# power_pcb.net
KiCad netlist of a schematic drawn in EAGLE
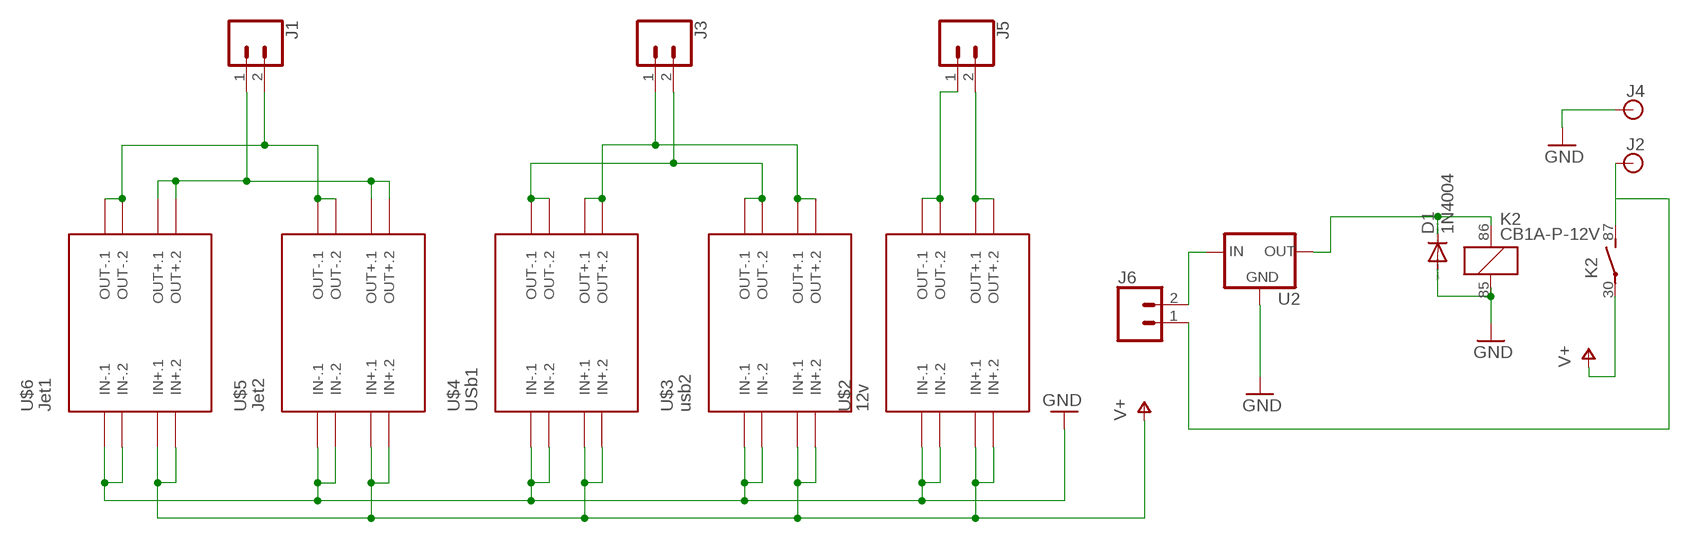
[diagram p0: schematic, sheet 1]

(export (version "E")
  (design (tool "Eeschema 10.0.6"))
  (components
    (comp (ref "D1")
      (value "1N4004")
      (footprint "eagle-import:DO41-10")
      (libsource (lib "eagle-import") (part "1N4004"))
    )
    (comp (ref "J1")
      (value "CONN_025MM")
      (footprint "eagle-import:SCREWTERMINAL-5MM-2")
      (libsource (lib "eagle-import") (part "CONN_025MM"))
    )
    (comp (ref "J2")
      (value "BANANA_CONN")
      (footprint "eagle-import:BANANA_CONN")
      (libsource (lib "eagle-import") (part "BANANA_CONN"))
    )
    (comp (ref "J3")
      (value "CONN_025MM")
      (footprint "eagle-import:SCREWTERMINAL-5MM-2")
      (libsource (lib "eagle-import") (part "CONN_025MM"))
    )
    (comp (ref "J4")
      (value "BANANA_CONN")
      (footprint "eagle-import:BANANA_CONN")
      (libsource (lib "eagle-import") (part "BANANA_CONN"))
    )
    (comp (ref "J5")
      (value "CONN_025MM")
      (footprint "eagle-import:SCREWTERMINAL-5MM-2")
      (libsource (lib "eagle-import") (part "CONN_025MM"))
    )
    (comp (ref "J6")
      (value "CONN_025MM")
      (footprint "eagle-import:SCREWTERMINAL-5MM-2")
      (libsource (lib "eagle-import") (part "CONN_025MM"))
    )
    (comp (ref "K2")
      (value "CB1A-P-12V")
      (footprint "eagle-import:CB1")
      (fields (field (name "MF") "AROMAT/ MATSUSHITA"))
      (libsource (lib "eagle-import") (part "CB1A-P-12V"))
    )
    (comp (ref "U$2")
      (value "12v")
      (footprint "eagle-import:DC-DC-STEP-DOWN-MP1584")
      (libsource (lib "eagle-import") (part "DC-DC-STEP-DOWN-MP1584"))
    )
    (comp (ref "U$3")
      (value "usb2")
      (footprint "eagle-import:DC-DC-STEP-DOWN-MP1584")
      (libsource (lib "eagle-import") (part "DC-DC-STEP-DOWN-MP1584"))
    )
    (comp (ref "U$4")
      (value "USb1")
      (footprint "eagle-import:DC-DC-STEP-DOWN-MP1584")
      (libsource (lib "eagle-import") (part "DC-DC-STEP-DOWN-MP1584"))
    )
    (comp (ref "U$5")
      (value "Jet2")
      (footprint "eagle-import:DC-DC-STEP-DOWN-MP1584")
      (libsource (lib "eagle-import") (part "DC-DC-STEP-DOWN-MP1584"))
    )
    (comp (ref "U$6")
      (value "Jet1")
      (footprint "eagle-import:DC-DC-STEP-DOWN-MP1584")
      (libsource (lib "eagle-import") (part "DC-DC-STEP-DOWN-MP1584"))
    )
    (comp (ref "U2")
      (value "V_REG_78XXSINK")
      (footprint "eagle-import:TO220-IGO")
      (libsource (lib "eagle-import") (part "V_REG_78XXSINK"))
    )
  )
  (nets
    (net (code "1") (name "GND") (class "Default")
      (node (ref "D1") (pin "A") (pinfunction "A_A") (pintype "passive"))
      (node (ref "J4") (pin "P$1") (pinfunction "1_P$1") (pintype "passive"))
      (node (ref "K2") (pin "85") (pinfunction "2_85") (pintype "passive"))
      (node (ref "U$2") (pin "IN-.1") (pinfunction "IN-.1_IN-.1") (pintype "bidirectional"))
      (node (ref "U$2") (pin "IN-.2") (pinfunction "IN-.2_IN-.2") (pintype "bidirectional"))
      (node (ref "U$3") (pin "IN-.1") (pinfunction "IN-.1_IN-.1") (pintype "bidirectional"))
      (node (ref "U$3") (pin "IN-.2") (pinfunction "IN-.2_IN-.2") (pintype "bidirectional"))
      (node (ref "U$4") (pin "IN-.1") (pinfunction "IN-.1_IN-.1") (pintype "bidirectional"))
      (node (ref "U$4") (pin "IN-.2") (pinfunction "IN-.2_IN-.2") (pintype "bidirectional"))
      (node (ref "U$5") (pin "IN-.1") (pinfunction "IN-.1_IN-.1") (pintype "bidirectional"))
      (node (ref "U$5") (pin "IN-.2") (pinfunction "IN-.2_IN-.2") (pintype "bidirectional"))
      (node (ref "U$6") (pin "IN-.1") (pinfunction "IN-.1_IN-.1") (pintype "bidirectional"))
      (node (ref "U$6") (pin "IN-.2") (pinfunction "IN-.2_IN-.2") (pintype "bidirectional"))
      (node (ref "U2") (pin "GND") (pinfunction "GND_GND") (pintype "input"))
    )
    (net (code "2") (name "Net-(J1-Pad1)") (class "Default")
      (node (ref "J1") (pin "1") (pinfunction "1_1") (pintype "passive"))
      (node (ref "U$5") (pin "OUT+.1") (pinfunction "OUT+.1_OUT+.1") (pintype "bidirectional"))
      (node (ref "U$5") (pin "OUT+.2") (pinfunction "OUT+.2_OUT+.2") (pintype "bidirectional"))
      (node (ref "U$6") (pin "OUT+.1") (pinfunction "OUT+.1_OUT+.1") (pintype "bidirectional"))
      (node (ref "U$6") (pin "OUT+.2") (pinfunction "OUT+.2_OUT+.2") (pintype "bidirectional"))
    )
    (net (code "3") (name "Net-(J1-Pad2)") (class "Default")
      (node (ref "J1") (pin "2") (pinfunction "2_2") (pintype "passive"))
      (node (ref "U$5") (pin "OUT-.1") (pinfunction "OUT-.1_OUT-.1") (pintype "bidirectional"))
      (node (ref "U$5") (pin "OUT-.2") (pinfunction "OUT-.2_OUT-.2") (pintype "bidirectional"))
      (node (ref "U$6") (pin "OUT-.1") (pinfunction "OUT-.1_OUT-.1") (pintype "bidirectional"))
      (node (ref "U$6") (pin "OUT-.2") (pinfunction "OUT-.2_OUT-.2") (pintype "bidirectional"))
    )
    (net (code "4") (name "Net-(J2-1)") (class "Default")
      (node (ref "J2") (pin "P$1") (pinfunction "1_P$1") (pintype "passive"))
      (node (ref "J6") (pin "1") (pinfunction "1_1") (pintype "passive"))
      (node (ref "K2") (pin "87") (pinfunction "S_87") (pintype "passive"))
    )
    (net (code "5") (name "Net-(J3-Pad1)") (class "Default")
      (node (ref "J3") (pin "1") (pinfunction "1_1") (pintype "passive"))
      (node (ref "U$3") (pin "OUT+.1") (pinfunction "OUT+.1_OUT+.1") (pintype "bidirectional"))
      (node (ref "U$3") (pin "OUT+.2") (pinfunction "OUT+.2_OUT+.2") (pintype "bidirectional"))
      (node (ref "U$4") (pin "OUT+.1") (pinfunction "OUT+.1_OUT+.1") (pintype "bidirectional"))
      (node (ref "U$4") (pin "OUT+.2") (pinfunction "OUT+.2_OUT+.2") (pintype "bidirectional"))
    )
    (net (code "6") (name "Net-(J3-Pad2)") (class "Default")
      (node (ref "J3") (pin "2") (pinfunction "2_2") (pintype "passive"))
      (node (ref "U$3") (pin "OUT-.1") (pinfunction "OUT-.1_OUT-.1") (pintype "bidirectional"))
      (node (ref "U$3") (pin "OUT-.2") (pinfunction "OUT-.2_OUT-.2") (pintype "bidirectional"))
      (node (ref "U$4") (pin "OUT-.1") (pinfunction "OUT-.1_OUT-.1") (pintype "bidirectional"))
      (node (ref "U$4") (pin "OUT-.2") (pinfunction "OUT-.2_OUT-.2") (pintype "bidirectional"))
    )
    (net (code "7") (name "Net-(J5-Pad1)") (class "Default")
      (node (ref "J5") (pin "1") (pinfunction "1_1") (pintype "passive"))
      (node (ref "U$2") (pin "OUT-.1") (pinfunction "OUT-.1_OUT-.1") (pintype "bidirectional"))
      (node (ref "U$2") (pin "OUT-.2") (pinfunction "OUT-.2_OUT-.2") (pintype "bidirectional"))
    )
    (net (code "8") (name "Net-(J5-Pad2)") (class "Default")
      (node (ref "J5") (pin "2") (pinfunction "2_2") (pintype "passive"))
      (node (ref "U$2") (pin "OUT+.1") (pinfunction "OUT+.1_OUT+.1") (pintype "bidirectional"))
      (node (ref "U$2") (pin "OUT+.2") (pinfunction "OUT+.2_OUT+.2") (pintype "bidirectional"))
    )
    (net (code "9") (name "Net-(J6-Pad2)") (class "Default")
      (node (ref "J6") (pin "2") (pinfunction "2_2") (pintype "passive"))
      (node (ref "U2") (pin "IN") (pinfunction "IN_IN") (pintype "input"))
    )
    (net (code "10") (name "Net-(K2A-1)") (class "Default")
      (node (ref "D1") (pin "C") (pinfunction "C_C") (pintype "passive"))
      (node (ref "K2") (pin "86") (pinfunction "1_86") (pintype "passive"))
      (node (ref "U2") (pin "OUT") (pinfunction "OUT_OUT") (pintype "passive"))
    )
    (net (code "11") (name "V+") (class "Default")
      (node (ref "K2") (pin "30") (pinfunction "P_30") (pintype "passive"))
      (node (ref "U$2") (pin "IN+.1") (pinfunction "IN+.1_IN+.1") (pintype "bidirectional"))
      (node (ref "U$2") (pin "IN+.2") (pinfunction "IN+.2_IN+.2") (pintype "bidirectional"))
      (node (ref "U$3") (pin "IN+.1") (pinfunction "IN+.1_IN+.1") (pintype "bidirectional"))
      (node (ref "U$3") (pin "IN+.2") (pinfunction "IN+.2_IN+.2") (pintype "bidirectional"))
      (node (ref "U$4") (pin "IN+.1") (pinfunction "IN+.1_IN+.1") (pintype "bidirectional"))
      (node (ref "U$4") (pin "IN+.2") (pinfunction "IN+.2_IN+.2") (pintype "bidirectional"))
      (node (ref "U$5") (pin "IN+.1") (pinfunction "IN+.1_IN+.1") (pintype "bidirectional"))
      (node (ref "U$5") (pin "IN+.2") (pinfunction "IN+.2_IN+.2") (pintype "bidirectional"))
      (node (ref "U$6") (pin "IN+.1") (pinfunction "IN+.1_IN+.1") (pintype "bidirectional"))
      (node (ref "U$6") (pin "IN+.2") (pinfunction "IN+.2_IN+.2") (pintype "bidirectional"))
    )
  )
)
